# WS2801_LED_Cascade.net
KiCad netlist of a schematic drawn in EAGLE
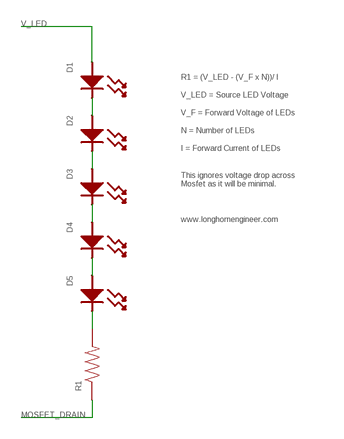
[diagram p0: schematic, sheet 1]

(export (version "E")
  (design (tool "Eeschema 10.0.6"))
  (components
    (comp (ref "D1")
      (value "LED_SINGLE0402")
      (footprint "eagle-import:LED_0402")
      (libsource (lib "eagle-import") (part "LED_SINGLE0402"))
    )
    (comp (ref "D2")
      (value "LED_SINGLE0402")
      (footprint "eagle-import:LED_0402")
      (libsource (lib "eagle-import") (part "LED_SINGLE0402"))
    )
    (comp (ref "D3")
      (value "LED_SINGLE0402")
      (footprint "eagle-import:LED_0402")
      (libsource (lib "eagle-import") (part "LED_SINGLE0402"))
    )
    (comp (ref "D4")
      (value "LED_SINGLE0402")
      (footprint "eagle-import:LED_0402")
      (libsource (lib "eagle-import") (part "LED_SINGLE0402"))
    )
    (comp (ref "D5")
      (value "LED_SINGLE0402")
      (footprint "eagle-import:LED_0402")
      (libsource (lib "eagle-import") (part "LED_SINGLE0402"))
    )
    (comp (ref "R1")
      (value "RESISTOR0402")
      (footprint "eagle-import:0402")
      (libsource (lib "eagle-import") (part "RESISTOR0402"))
    )
  )
  (nets
    (net (code "1") (name "/MOSFET_DRAIN") (class "Default")
      (node (ref "R1") (pin "1") (pinfunction "1_1") (pintype "passive"))
    )
    (net (code "2") (name "/V_LED") (class "Default")
      (node (ref "D1") (pin "ANODE") (pinfunction "ANODE_ANODE") (pintype "bidirectional"))
    )
    (net (code "3") (name "Net-(D1-PadCATHODE)") (class "Default")
      (node (ref "D1") (pin "CATHODE") (pinfunction "CATHODE_CATHODE") (pintype "bidirectional"))
      (node (ref "D2") (pin "ANODE") (pinfunction "ANODE_ANODE") (pintype "bidirectional"))
    )
    (net (code "4") (name "Net-(D2-PadCATHODE)") (class "Default")
      (node (ref "D2") (pin "CATHODE") (pinfunction "CATHODE_CATHODE") (pintype "bidirectional"))
      (node (ref "D3") (pin "ANODE") (pinfunction "ANODE_ANODE") (pintype "bidirectional"))
    )
    (net (code "5") (name "Net-(D3-PadCATHODE)") (class "Default")
      (node (ref "D3") (pin "CATHODE") (pinfunction "CATHODE_CATHODE") (pintype "bidirectional"))
      (node (ref "D4") (pin "ANODE") (pinfunction "ANODE_ANODE") (pintype "bidirectional"))
    )
    (net (code "6") (name "Net-(D4-PadCATHODE)") (class "Default")
      (node (ref "D4") (pin "CATHODE") (pinfunction "CATHODE_CATHODE") (pintype "bidirectional"))
      (node (ref "D5") (pin "ANODE") (pinfunction "ANODE_ANODE") (pintype "bidirectional"))
    )
    (net (code "7") (name "Net-(D5-PadCATHODE)") (class "Default")
      (node (ref "D5") (pin "CATHODE") (pinfunction "CATHODE_CATHODE") (pintype "bidirectional"))
      (node (ref "R1") (pin "2") (pinfunction "2_2") (pintype "passive"))
    )
  )
)
